# driver.net
KiCad netlist of a schematic drawn in EAGLE
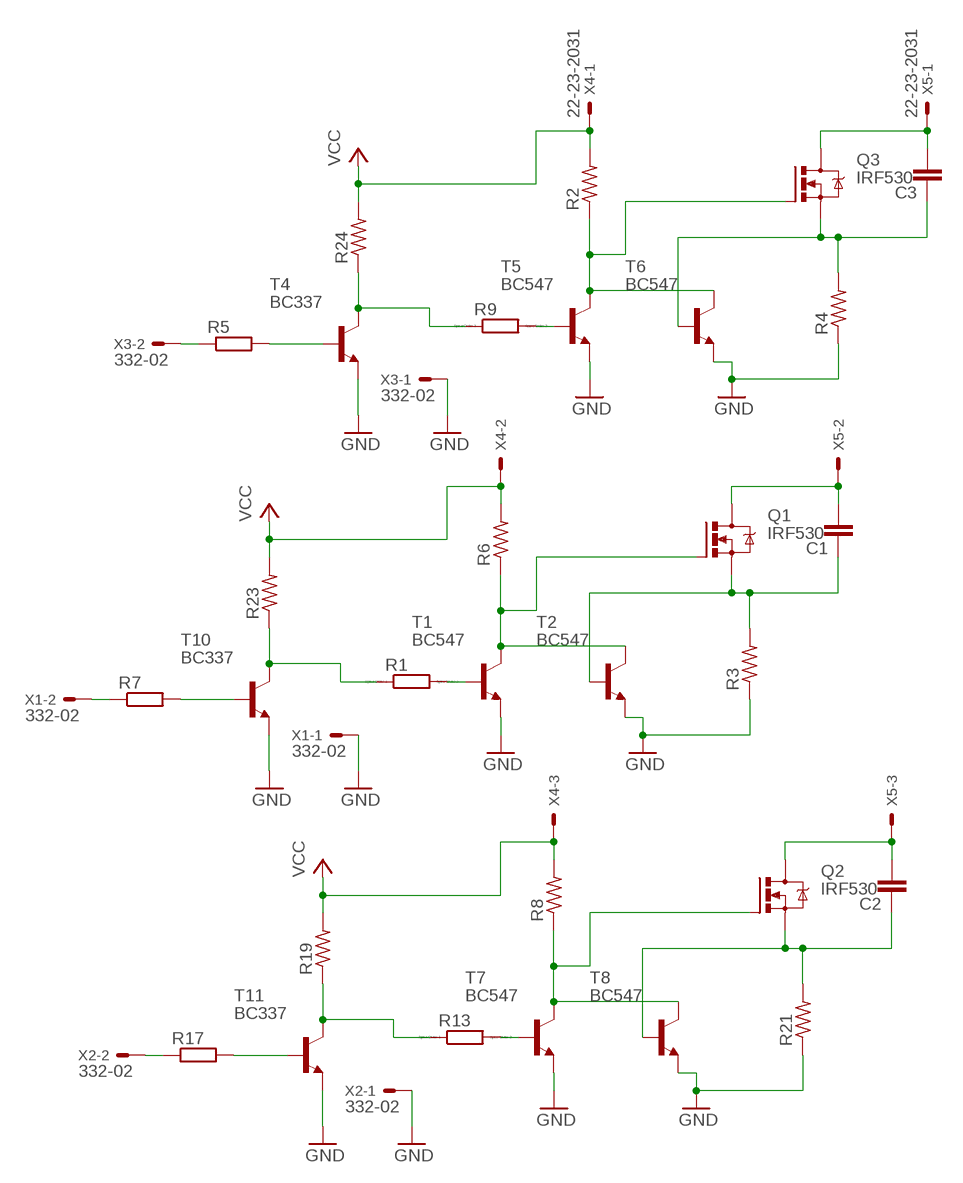
[diagram p0: schematic, sheet 1]

(export (version "E")
  (design (tool "Eeschema 10.0.6"))
  (components
    (comp (ref "C1")
      (value "C-EU025-025X050")
      (footprint "eagle-import:C025-025X050")
      (libsource (lib "eagle-import") (part "C-EU025-025X050"))
    )
    (comp (ref "C2")
      (value "C-EU025-025X050")
      (footprint "eagle-import:C025-025X050")
      (libsource (lib "eagle-import") (part "C-EU025-025X050"))
    )
    (comp (ref "C3")
      (value "C-EU025-025X050")
      (footprint "eagle-import:C025-025X050")
      (libsource (lib "eagle-import") (part "C-EU025-025X050"))
    )
    (comp (ref "Q1")
      (value "IRF530")
      (footprint "eagle-import:TO220BV")
      (libsource (lib "eagle-import") (part "IRF530"))
    )
    (comp (ref "Q2")
      (value "IRF530")
      (footprint "eagle-import:TO220BV")
      (libsource (lib "eagle-import") (part "IRF530"))
    )
    (comp (ref "Q3")
      (value "IRF530")
      (footprint "eagle-import:TO220BV")
      (libsource (lib "eagle-import") (part "IRF530"))
    )
    (comp (ref "R1")
      (value "R0204/7")
      (footprint "eagle-import:0204_7")
      (libsource (lib "eagle-import") (part "R0204/7"))
    )
    (comp (ref "R2")
      (value "R-US_0309/10")
      (footprint "eagle-import:0309_10")
      (libsource (lib "eagle-import") (part "R-US_0309/10"))
    )
    (comp (ref "R3")
      (value "R-US_0817/22")
      (footprint "eagle-import:P0817_22")
      (libsource (lib "eagle-import") (part "R-US_0817/22"))
    )
    (comp (ref "R4")
      (value "R-US_0817/22")
      (footprint "eagle-import:P0817_22")
      (libsource (lib "eagle-import") (part "R-US_0817/22"))
    )
    (comp (ref "R5")
      (value "R-EU_0204/7")
      (footprint "eagle-import:0204_7")
      (libsource (lib "eagle-import") (part "R-EU_0204/7"))
    )
    (comp (ref "R6")
      (value "R-US_0309/10")
      (footprint "eagle-import:0309_10")
      (libsource (lib "eagle-import") (part "R-US_0309/10"))
    )
    (comp (ref "R7")
      (value "R-EU_0204/7")
      (footprint "eagle-import:0204_7")
      (libsource (lib "eagle-import") (part "R-EU_0204/7"))
    )
    (comp (ref "R8")
      (value "R-US_0309/10")
      (footprint "eagle-import:0309_10")
      (libsource (lib "eagle-import") (part "R-US_0309/10"))
    )
    (comp (ref "R9")
      (value "R0204/7")
      (footprint "eagle-import:0204_7")
      (libsource (lib "eagle-import") (part "R0204/7"))
    )
    (comp (ref "R13")
      (value "R0204/7")
      (footprint "eagle-import:0204_7")
      (libsource (lib "eagle-import") (part "R0204/7"))
    )
    (comp (ref "R17")
      (value "R-EU_0204/7")
      (footprint "eagle-import:0204_7")
      (libsource (lib "eagle-import") (part "R-EU_0204/7"))
    )
    (comp (ref "R19")
      (value "R-US_0309/10")
      (footprint "eagle-import:0309_10")
      (libsource (lib "eagle-import") (part "R-US_0309/10"))
    )
    (comp (ref "R21")
      (value "R-US_0817/22")
      (footprint "eagle-import:P0817_22")
      (libsource (lib "eagle-import") (part "R-US_0817/22"))
    )
    (comp (ref "R23")
      (value "R-US_0309/10")
      (footprint "eagle-import:0309_10")
      (libsource (lib "eagle-import") (part "R-US_0309/10"))
    )
    (comp (ref "R24")
      (value "R-US_0309/10")
      (footprint "eagle-import:0309_10")
      (libsource (lib "eagle-import") (part "R-US_0309/10"))
    )
    (comp (ref "T1")
      (value "BC547")
      (footprint "eagle-import:TO92")
      (libsource (lib "eagle-import") (part "BC547"))
    )
    (comp (ref "T2")
      (value "BC547")
      (footprint "eagle-import:TO92")
      (libsource (lib "eagle-import") (part "BC547"))
    )
    (comp (ref "T4")
      (value "BC337")
      (footprint "eagle-import:TO92")
      (libsource (lib "eagle-import") (part "BC337"))
    )
    (comp (ref "T5")
      (value "BC547")
      (footprint "eagle-import:TO92")
      (libsource (lib "eagle-import") (part "BC547"))
    )
    (comp (ref "T6")
      (value "BC547")
      (footprint "eagle-import:TO92")
      (libsource (lib "eagle-import") (part "BC547"))
    )
    (comp (ref "T7")
      (value "BC547")
      (footprint "eagle-import:TO92")
      (libsource (lib "eagle-import") (part "BC547"))
    )
    (comp (ref "T8")
      (value "BC547")
      (footprint "eagle-import:TO92")
      (libsource (lib "eagle-import") (part "BC547"))
    )
    (comp (ref "T10")
      (value "BC337")
      (footprint "eagle-import:TO92")
      (libsource (lib "eagle-import") (part "BC337"))
    )
    (comp (ref "T11")
      (value "BC337")
      (footprint "eagle-import:TO92")
      (libsource (lib "eagle-import") (part "BC337"))
    )
    (comp (ref "X1")
      (value "332-02")
      (footprint "eagle-import:332-02")
      (libsource (lib "eagle-import") (part "332-02"))
    )
    (comp (ref "X2")
      (value "332-02")
      (footprint "eagle-import:332-02")
      (libsource (lib "eagle-import") (part "332-02"))
    )
    (comp (ref "X3")
      (value "332-02")
      (footprint "eagle-import:332-02")
      (libsource (lib "eagle-import") (part "332-02"))
    )
    (comp (ref "X4")
      (value "22-23-2031")
      (footprint "eagle-import:22-23-2031")
      (fields (field (name "MF") "MOLEX"))
      (libsource (lib "eagle-import") (part "22-23-2031"))
    )
    (comp (ref "X5")
      (value "22-23-2031")
      (footprint "eagle-import:22-23-2031")
      (fields (field (name "MF") "MOLEX"))
      (libsource (lib "eagle-import") (part "22-23-2031"))
    )
  )
  (nets
    (net (code "1") (name "GND") (class "Default")
      (node (ref "R21") (pin "1") (pinfunction "1_1") (pintype "passive"))
      (node (ref "R3") (pin "1") (pinfunction "1_1") (pintype "passive"))
      (node (ref "R4") (pin "1") (pinfunction "1_1") (pintype "passive"))
      (node (ref "T1") (pin "1") (pinfunction "E_1") (pintype "passive"))
      (node (ref "T10") (pin "1") (pinfunction "E_1") (pintype "passive"))
      (node (ref "T11") (pin "1") (pinfunction "E_1") (pintype "passive"))
      (node (ref "T2") (pin "1") (pinfunction "E_1") (pintype "passive"))
      (node (ref "T4") (pin "1") (pinfunction "E_1") (pintype "passive"))
      (node (ref "T5") (pin "1") (pinfunction "E_1") (pintype "passive"))
      (node (ref "T6") (pin "1") (pinfunction "E_1") (pintype "passive"))
      (node (ref "T7") (pin "1") (pinfunction "E_1") (pintype "passive"))
      (node (ref "T8") (pin "1") (pinfunction "E_1") (pintype "passive"))
      (node (ref "X1") (pin "1") (pinfunction "S_1") (pintype "passive"))
      (node (ref "X2") (pin "1") (pinfunction "S_1") (pintype "passive"))
      (node (ref "X3") (pin "1") (pinfunction "S_1") (pintype "passive"))
    )
    (net (code "2") (name "Net-(T1-B)") (class "Default")
      (node (ref "R1") (pin "2") (pinfunction "2_2") (pintype "passive"))
      (node (ref "T1") (pin "2") (pinfunction "B_2") (pintype "passive"))
    )
    (net (code "3") (name "Net-(T1-C)") (class "Default")
      (node (ref "Q1") (pin "G") (pinfunction "G_G") (pintype "passive"))
      (node (ref "R6") (pin "1") (pinfunction "1_1") (pintype "passive"))
      (node (ref "T1") (pin "3") (pinfunction "C_3") (pintype "passive"))
      (node (ref "T2") (pin "3") (pinfunction "C_3") (pintype "passive"))
    )
    (net (code "4") (name "Net-(T2-B)") (class "Default")
      (node (ref "C1") (pin "1") (pinfunction "1_1") (pintype "passive"))
      (node (ref "Q1") (pin "S") (pinfunction "S_S") (pintype "passive"))
      (node (ref "R3") (pin "2") (pinfunction "2_2") (pintype "passive"))
      (node (ref "T2") (pin "2") (pinfunction "B_2") (pintype "passive"))
    )
    (net (code "5") (name "Net-(T4-B)") (class "Default")
      (node (ref "R5") (pin "2") (pinfunction "2_2") (pintype "passive"))
      (node (ref "T4") (pin "2") (pinfunction "B_2") (pintype "passive"))
    )
    (net (code "6") (name "Net-(T4-C)") (class "Default")
      (node (ref "R24") (pin "1") (pinfunction "1_1") (pintype "passive"))
      (node (ref "R9") (pin "1") (pinfunction "1_1") (pintype "passive"))
      (node (ref "T4") (pin "3") (pinfunction "C_3") (pintype "passive"))
    )
    (net (code "7") (name "Net-(T5-B)") (class "Default")
      (node (ref "R9") (pin "2") (pinfunction "2_2") (pintype "passive"))
      (node (ref "T5") (pin "2") (pinfunction "B_2") (pintype "passive"))
    )
    (net (code "8") (name "Net-(T5-C)") (class "Default")
      (node (ref "Q3") (pin "G") (pinfunction "G_G") (pintype "passive"))
      (node (ref "R2") (pin "1") (pinfunction "1_1") (pintype "passive"))
      (node (ref "T5") (pin "3") (pinfunction "C_3") (pintype "passive"))
      (node (ref "T6") (pin "3") (pinfunction "C_3") (pintype "passive"))
    )
    (net (code "9") (name "Net-(T6-B)") (class "Default")
      (node (ref "C3") (pin "1") (pinfunction "1_1") (pintype "passive"))
      (node (ref "Q3") (pin "S") (pinfunction "S_S") (pintype "passive"))
      (node (ref "R4") (pin "2") (pinfunction "2_2") (pintype "passive"))
      (node (ref "T6") (pin "2") (pinfunction "B_2") (pintype "passive"))
    )
    (net (code "10") (name "Net-(T7-B)") (class "Default")
      (node (ref "R13") (pin "2") (pinfunction "2_2") (pintype "passive"))
      (node (ref "T7") (pin "2") (pinfunction "B_2") (pintype "passive"))
    )
    (net (code "11") (name "Net-(T7-C)") (class "Default")
      (node (ref "Q2") (pin "G") (pinfunction "G_G") (pintype "passive"))
      (node (ref "R8") (pin "1") (pinfunction "1_1") (pintype "passive"))
      (node (ref "T7") (pin "3") (pinfunction "C_3") (pintype "passive"))
      (node (ref "T8") (pin "3") (pinfunction "C_3") (pintype "passive"))
    )
    (net (code "12") (name "Net-(T8-B)") (class "Default")
      (node (ref "C2") (pin "1") (pinfunction "1_1") (pintype "passive"))
      (node (ref "Q2") (pin "S") (pinfunction "S_S") (pintype "passive"))
      (node (ref "R21") (pin "2") (pinfunction "2_2") (pintype "passive"))
      (node (ref "T8") (pin "2") (pinfunction "B_2") (pintype "passive"))
    )
    (net (code "13") (name "Net-(T10-B)") (class "Default")
      (node (ref "R7") (pin "2") (pinfunction "2_2") (pintype "passive"))
      (node (ref "T10") (pin "2") (pinfunction "B_2") (pintype "passive"))
    )
    (net (code "14") (name "Net-(T10-C)") (class "Default")
      (node (ref "R1") (pin "1") (pinfunction "1_1") (pintype "passive"))
      (node (ref "R23") (pin "1") (pinfunction "1_1") (pintype "passive"))
      (node (ref "T10") (pin "3") (pinfunction "C_3") (pintype "passive"))
    )
    (net (code "15") (name "Net-(T11-B)") (class "Default")
      (node (ref "R17") (pin "2") (pinfunction "2_2") (pintype "passive"))
      (node (ref "T11") (pin "2") (pinfunction "B_2") (pintype "passive"))
    )
    (net (code "16") (name "Net-(T11-C)") (class "Default")
      (node (ref "R13") (pin "1") (pinfunction "1_1") (pintype "passive"))
      (node (ref "R19") (pin "1") (pinfunction "1_1") (pintype "passive"))
      (node (ref "T11") (pin "3") (pinfunction "C_3") (pintype "passive"))
    )
    (net (code "17") (name "Net-(X1B-S)") (class "Default")
      (node (ref "R7") (pin "1") (pinfunction "1_1") (pintype "passive"))
      (node (ref "X1") (pin "2") (pinfunction "S_2") (pintype "passive"))
    )
    (net (code "18") (name "Net-(X2B-S)") (class "Default")
      (node (ref "R17") (pin "1") (pinfunction "1_1") (pintype "passive"))
      (node (ref "X2") (pin "2") (pinfunction "S_2") (pintype "passive"))
    )
    (net (code "19") (name "Net-(X3B-S)") (class "Default")
      (node (ref "R5") (pin "1") (pinfunction "1_1") (pintype "passive"))
      (node (ref "X3") (pin "2") (pinfunction "S_2") (pintype "passive"))
    )
    (net (code "20") (name "Net-(X5A-S)") (class "Default")
      (node (ref "C3") (pin "2") (pinfunction "2_2") (pintype "passive"))
      (node (ref "Q3") (pin "D") (pinfunction "D_D") (pintype "passive"))
      (node (ref "X5") (pin "1") (pinfunction "S_1") (pintype "passive"))
    )
    (net (code "21") (name "Net-(X5B-S)") (class "Default")
      (node (ref "C1") (pin "2") (pinfunction "2_2") (pintype "passive"))
      (node (ref "Q1") (pin "D") (pinfunction "D_D") (pintype "passive"))
      (node (ref "X5") (pin "2") (pinfunction "S_2") (pintype "passive"))
    )
    (net (code "22") (name "Net-(X5C-S)") (class "Default")
      (node (ref "C2") (pin "2") (pinfunction "2_2") (pintype "passive"))
      (node (ref "Q2") (pin "D") (pinfunction "D_D") (pintype "passive"))
      (node (ref "X5") (pin "3") (pinfunction "S_3") (pintype "passive"))
    )
    (net (code "23") (name "VCC") (class "Default")
      (node (ref "R19") (pin "2") (pinfunction "2_2") (pintype "passive"))
      (node (ref "R2") (pin "2") (pinfunction "2_2") (pintype "passive"))
      (node (ref "R23") (pin "2") (pinfunction "2_2") (pintype "passive"))
      (node (ref "R24") (pin "2") (pinfunction "2_2") (pintype "passive"))
      (node (ref "R6") (pin "2") (pinfunction "2_2") (pintype "passive"))
      (node (ref "R8") (pin "2") (pinfunction "2_2") (pintype "passive"))
      (node (ref "X4") (pin "1") (pinfunction "S_1") (pintype "passive"))
      (node (ref "X4") (pin "2") (pinfunction "S_2") (pintype "passive"))
      (node (ref "X4") (pin "3") (pinfunction "S_3") (pintype "passive"))
    )
  )
)
